# syma-wireless-charger.net
KiCad netlist of a schematic drawn in EAGLE
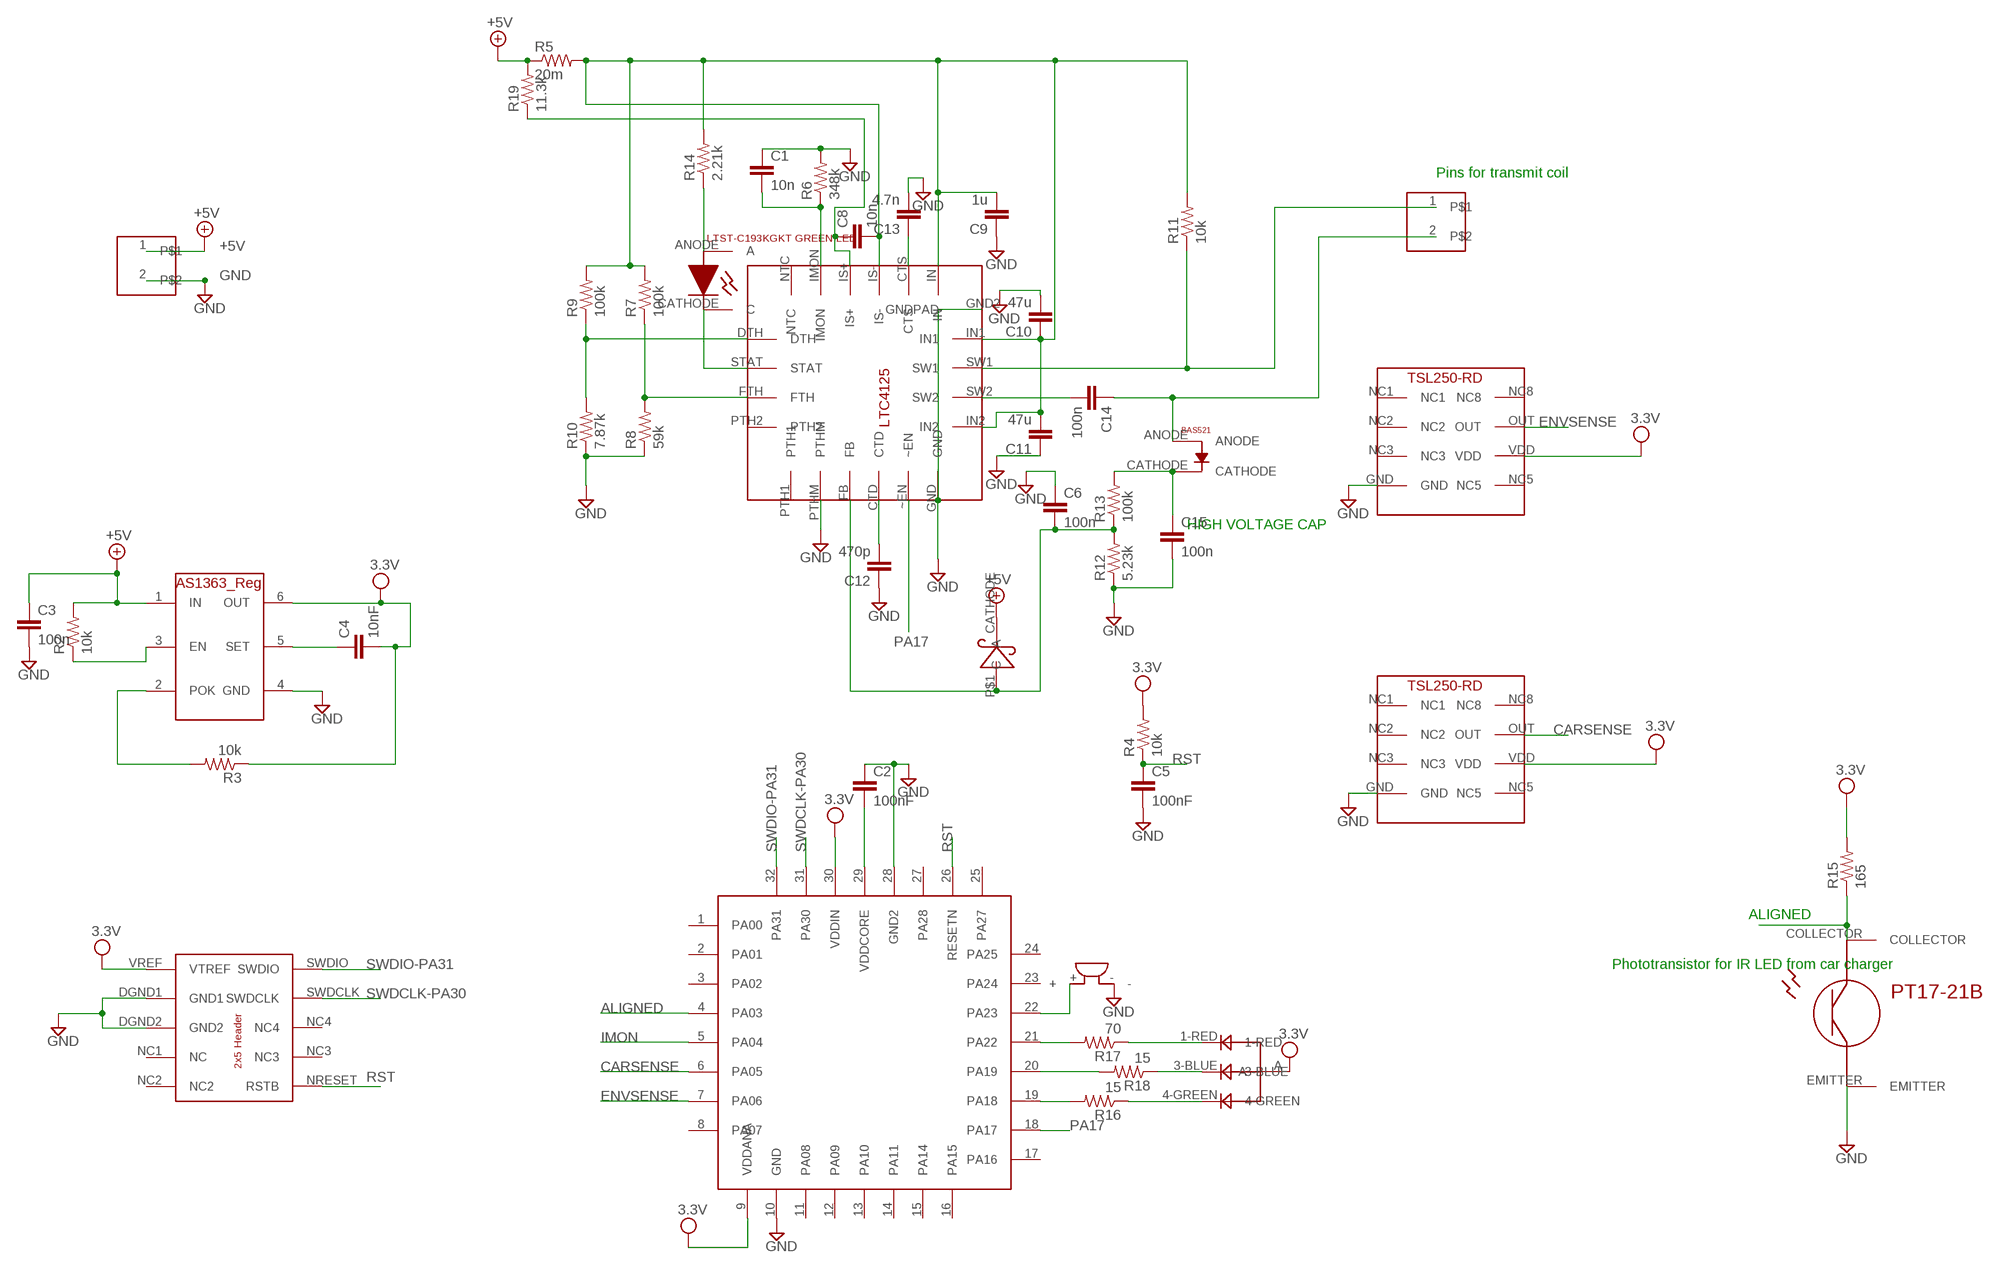
[diagram p0: schematic, sheet 1]

(export (version "E")
  (design (tool "Eeschema 10.0.6"))
  (components
    (comp (ref "C1")
      (value "10n")
      (footprint "eagle-import:C0805")
      (libsource (lib "eagle-import") (part "C-EUC0805"))
    )
    (comp (ref "C2")
      (value "100nF")
      (footprint "eagle-import:C0805K")
      (libsource (lib "eagle-import") (part "resistor_C-EUC0805K"))
    )
    (comp (ref "C3")
      (value "100n")
      (footprint "eagle-import:C0805K")
      (libsource (lib "eagle-import") (part "resistor_C-EUC0805K"))
    )
    (comp (ref "C4")
      (value "10nF")
      (footprint "eagle-import:C0805K")
      (libsource (lib "eagle-import") (part "resistor_C-EUC0805K"))
    )
    (comp (ref "C5")
      (value "100nF")
      (footprint "eagle-import:C0805K")
      (libsource (lib "eagle-import") (part "resistor_C-EUC0805K"))
    )
    (comp (ref "C6")
      (value "100n")
      (footprint "eagle-import:C0805")
      (libsource (lib "eagle-import") (part "C-EUC0805"))
    )
    (comp (ref "C8")
      (value "10n")
      (footprint "eagle-import:C0805")
      (libsource (lib "eagle-import") (part "C-EUC0805"))
    )
    (comp (ref "C9")
      (value "1u")
      (footprint "eagle-import:C0805")
      (libsource (lib "eagle-import") (part "C-EUC0805"))
    )
    (comp (ref "C10")
      (value "47u")
      (footprint "eagle-import:C0805")
      (libsource (lib "eagle-import") (part "C-EUC0805"))
    )
    (comp (ref "C11")
      (value "47u")
      (footprint "eagle-import:C0805")
      (libsource (lib "eagle-import") (part "C-EUC0805"))
    )
    (comp (ref "C12")
      (value "470p")
      (footprint "eagle-import:C0805")
      (libsource (lib "eagle-import") (part "C-EUC0805"))
    )
    (comp (ref "C13")
      (value "4.7n")
      (footprint "eagle-import:C0805")
      (libsource (lib "eagle-import") (part "C-EUC0805"))
    )
    (comp (ref "C14")
      (value "100n")
      (footprint "eagle-import:C1206")
      (libsource (lib "eagle-import") (part "C-EUC1206"))
    )
    (comp (ref "C15")
      (value "100n")
      (footprint "eagle-import:C0603")
      (libsource (lib "eagle-import") (part "resistor_C-EUC0603"))
    )
    (comp (ref "DBG1")
      (value "DEBUGHEAD")
      (footprint "eagle-import:DEBUGHEAD")
      (libsource (lib "eagle-import") (part "DEBUGHEAD"))
    )
    (comp (ref "R2")
      (value "10k")
      (footprint "eagle-import:R0805")
      (libsource (lib "eagle-import") (part "resistor_R-US_R0805"))
    )
    (comp (ref "R3")
      (value "10k")
      (footprint "eagle-import:R0805")
      (libsource (lib "eagle-import") (part "resistor_R-US_R0805"))
    )
    (comp (ref "R4")
      (value "10k")
      (footprint "eagle-import:R0805")
      (libsource (lib "eagle-import") (part "resistor_R-US_R0805"))
    )
    (comp (ref "R5")
      (value "20m")
      (footprint "eagle-import:R0805")
      (libsource (lib "eagle-import") (part "R-US_R0805"))
    )
    (comp (ref "R6")
      (value "348k")
      (footprint "eagle-import:R0805")
      (libsource (lib "eagle-import") (part "R-US_R0805"))
    )
    (comp (ref "R7")
      (value "100k")
      (footprint "eagle-import:R0805")
      (libsource (lib "eagle-import") (part "R-US_R0805"))
    )
    (comp (ref "R8")
      (value "59k")
      (footprint "eagle-import:R0805")
      (libsource (lib "eagle-import") (part "R-US_R0805"))
    )
    (comp (ref "R9")
      (value "100k")
      (footprint "eagle-import:R0805")
      (libsource (lib "eagle-import") (part "R-US_R0805"))
    )
    (comp (ref "R10")
      (value "7.87k")
      (footprint "eagle-import:R0805")
      (libsource (lib "eagle-import") (part "R-US_R0805"))
    )
    (comp (ref "R11")
      (value "10k")
      (footprint "eagle-import:R0805")
      (libsource (lib "eagle-import") (part "R-US_R0805"))
    )
    (comp (ref "R12")
      (value "5.23k")
      (footprint "eagle-import:R0805")
      (libsource (lib "eagle-import") (part "R-US_R0805"))
    )
    (comp (ref "R13")
      (value "100k")
      (footprint "eagle-import:R0805")
      (libsource (lib "eagle-import") (part "R-US_R0805"))
    )
    (comp (ref "R14")
      (value "2.21k")
      (footprint "eagle-import:R0805")
      (libsource (lib "eagle-import") (part "R-US_R0805"))
    )
    (comp (ref "R15")
      (value "165")
      (footprint "eagle-import:R0805")
      (libsource (lib "eagle-import") (part "resistor_R-US_R0805"))
    )
    (comp (ref "R16")
      (value "15")
      (footprint "eagle-import:R0805")
      (libsource (lib "eagle-import") (part "resistor_R-US_R0805"))
    )
    (comp (ref "R17")
      (value "70")
      (footprint "eagle-import:R0805")
      (libsource (lib "eagle-import") (part "resistor_R-US_R0805"))
    )
    (comp (ref "R18")
      (value "15")
      (footprint "eagle-import:R0805")
      (libsource (lib "eagle-import") (part "resistor_R-US_R0805"))
    )
    (comp (ref "R19")
      (value "11.3k")
      (footprint "eagle-import:R0805")
      (libsource (lib "eagle-import") (part "R-US_R0805"))
    )
    (comp (ref "U$1")
      (value "LTC4125")
      (footprint "eagle-import:LTC1945-QFN")
      (libsource (lib "eagle-import") (part "LTC4125"))
    )
    (comp (ref "U$2")
      (value "BAS521")
      (footprint "eagle-import:BAS521-V-DIODE")
      (libsource (lib "eagle-import") (part "BAS521"))
    )
    (comp (ref "U$3")
      (value "1X02")
      (footprint "eagle-import:1X02")
      (libsource (lib "eagle-import") (part "1X02"))
    )
    (comp (ref "U$4")
      (value "RGBLED")
      (footprint "eagle-import:RGBLED")
      (libsource (lib "eagle-import") (part "RGBLED"))
    )
    (comp (ref "U$5")
      (value "BUZZER")
      (footprint "eagle-import:BUZZER")
      (libsource (lib "eagle-import") (part "BUZZER"))
    )
    (comp (ref "U$6")
      (value "TSL250-RD")
      (footprint "eagle-import:TSL250-RD")
      (libsource (lib "eagle-import") (part "TSL250-RD"))
    )
    (comp (ref "U$7")
      (value "TSL250-RD")
      (footprint "eagle-import:TSL250-RD")
      (libsource (lib "eagle-import") (part "TSL250-RD"))
    )
    (comp (ref "U$8")
      (value "SCHTKYDIODE-523")
      (footprint "eagle-import:SOD-523")
      (libsource (lib "eagle-import") (part "SCHTKYDIODE-523"))
    )
    (comp (ref "U$9")
      (value "LTST-C193KGKT_GREEN-LED")
      (footprint "eagle-import:LTST-C193KGKT_GREEN-LED")
      (libsource (lib "eagle-import") (part "LTST-C193KGKT_GREEN-LED"))
    )
    (comp (ref "U$10")
      (value "PT17-21B_PHOTOTRANSISTOR")
      (footprint "eagle-import:PT17-21B_PHOTOTRANSISTOR")
      (libsource (lib "eagle-import") (part "PT17-21B_PHOTOTRANSISTOR"))
    )
    (comp (ref "U$11")
      (value "1X02")
      (footprint "eagle-import:1X02")
      (libsource (lib "eagle-import") (part "1X02"))
    )
    (comp (ref "U1")
      (value "SAMD21E")
      (footprint "eagle-import:TQFP32-08")
      (libsource (lib "eagle-import") (part "SAMD21E"))
    )
    (comp (ref "U2")
      (value "3.3V_AS1363")
      (footprint "eagle-import:SOT23-6")
      (libsource (lib "eagle-import") (part "3.3V_AS1363"))
    )
  )
  (nets
    (net (code "1") (name "+5V") (class "Default")
      (node (ref "C3") (pin "1") (pinfunction "1_1") (pintype "passive"))
      (node (ref "R19") (pin "2") (pinfunction "2_2") (pintype "passive"))
      (node (ref "R2") (pin "2") (pinfunction "2_2") (pintype "passive"))
      (node (ref "R5") (pin "1") (pinfunction "1_1") (pintype "passive"))
      (node (ref "U$3") (pin "1") (pinfunction "P$1_1") (pintype "bidirectional"))
      (node (ref "U$8") (pin "CATHODE") (pinfunction "C_CATHODE") (pintype "bidirectional"))
      (node (ref "U2") (pin "1") (pinfunction "IN_1") (pintype "bidirectional"))
    )
    (net (code "2") (name "/ALIGNED") (class "Default")
      (node (ref "R15") (pin "1") (pinfunction "1_1") (pintype "passive"))
      (node (ref "U$10") (pin "COLLECTOR") (pinfunction "COLLECTOR_COLLECTOR") (pintype "bidirectional"))
      (node (ref "U1") (pin "4") (pinfunction "PA03_4") (pintype "bidirectional"))
    )
    (net (code "3") (name "/CARSENSE") (class "Default")
      (node (ref "U$6") (pin "OUT") (pinfunction "OUT_OUT") (pintype "bidirectional"))
      (node (ref "U1") (pin "6") (pinfunction "PA05_6") (pintype "bidirectional"))
    )
    (net (code "4") (name "/ENVSENSE") (class "Default")
      (node (ref "U$7") (pin "OUT") (pinfunction "OUT_OUT") (pintype "bidirectional"))
      (node (ref "U1") (pin "7") (pinfunction "PA06_7") (pintype "bidirectional"))
    )
    (net (code "5") (name "/IMON") (class "Default")
      (node (ref "C1") (pin "2") (pinfunction "2_2") (pintype "passive"))
      (node (ref "R6") (pin "1") (pinfunction "1_1") (pintype "passive"))
      (node (ref "U$1") (pin "IMON") (pinfunction "IMON_IMON") (pintype "bidirectional"))
      (node (ref "U1") (pin "5") (pinfunction "PA04_5") (pintype "bidirectional"))
    )
    (net (code "6") (name "/PA17") (class "Default")
      (node (ref "U$1") (pin "~EN") (pinfunction "~{EN}_~EN") (pintype "bidirectional"))
      (node (ref "U1") (pin "18") (pinfunction "PA17_18") (pintype "bidirectional"))
    )
    (net (code "7") (name "/RST") (class "Default")
      (node (ref "C5") (pin "1") (pinfunction "1_1") (pintype "passive"))
      (node (ref "DBG1") (pin "NRESET") (pinfunction "RSTB_NRESET") (pintype "bidirectional"))
      (node (ref "R4") (pin "1") (pinfunction "1_1") (pintype "passive"))
      (node (ref "U1") (pin "26") (pinfunction "RESETN_26") (pintype "bidirectional"))
    )
    (net (code "8") (name "/SWDCLK-PA30") (class "Default")
      (node (ref "DBG1") (pin "SWDCLK") (pinfunction "SWDCLK_SWDCLK") (pintype "bidirectional"))
      (node (ref "U1") (pin "31") (pinfunction "PA30_31") (pintype "bidirectional"))
    )
    (net (code "9") (name "/SWDIO-PA31") (class "Default")
      (node (ref "DBG1") (pin "SWDIO") (pinfunction "SWDIO_SWDIO") (pintype "bidirectional"))
      (node (ref "U1") (pin "32") (pinfunction "PA31_32") (pintype "bidirectional"))
    )
    (net (code "10") (name "3.3V") (class "Default")
      (node (ref "C4") (pin "2") (pinfunction "2_2") (pintype "passive"))
      (node (ref "DBG1") (pin "VREF") (pinfunction "VTREF_VREF") (pintype "bidirectional"))
      (node (ref "R15") (pin "2") (pinfunction "2_2") (pintype "passive"))
      (node (ref "R3") (pin "1") (pinfunction "1_1") (pintype "passive"))
      (node (ref "R4") (pin "2") (pinfunction "2_2") (pintype "passive"))
      (node (ref "U$4") (pin "A") (pinfunction "A_A") (pintype "bidirectional"))
      (node (ref "U$6") (pin "VDD") (pinfunction "VDD_VDD") (pintype "bidirectional"))
      (node (ref "U$7") (pin "VDD") (pinfunction "VDD_VDD") (pintype "bidirectional"))
      (node (ref "U1") (pin "30") (pinfunction "VDDIN_30") (pintype "bidirectional"))
      (node (ref "U1") (pin "9") (pinfunction "VDDANA_9") (pintype "bidirectional"))
      (node (ref "U2") (pin "6") (pinfunction "OUT_6") (pintype "bidirectional"))
    )
    (net (code "11") (name "GND") (class "Default")
      (node (ref "C1") (pin "1") (pinfunction "1_1") (pintype "passive"))
      (node (ref "C10") (pin "2") (pinfunction "2_2") (pintype "passive"))
      (node (ref "C11") (pin "1") (pinfunction "1_1") (pintype "passive"))
      (node (ref "C12") (pin "1") (pinfunction "1_1") (pintype "passive"))
      (node (ref "C13") (pin "2") (pinfunction "2_2") (pintype "passive"))
      (node (ref "C15") (pin "2") (pinfunction "2_2") (pintype "passive"))
      (node (ref "C2") (pin "1") (pinfunction "1_1") (pintype "passive"))
      (node (ref "C3") (pin "2") (pinfunction "2_2") (pintype "passive"))
      (node (ref "C5") (pin "2") (pinfunction "2_2") (pintype "passive"))
      (node (ref "C6") (pin "1") (pinfunction "1_1") (pintype "passive"))
      (node (ref "C9") (pin "1") (pinfunction "1_1") (pintype "passive"))
      (node (ref "DBG1") (pin "DGND1") (pinfunction "GND1_DGND1") (pintype "bidirectional"))
      (node (ref "DBG1") (pin "DGND2") (pinfunction "GND2_DGND2") (pintype "bidirectional"))
      (node (ref "R10") (pin "1") (pinfunction "1_1") (pintype "passive"))
      (node (ref "R12") (pin "1") (pinfunction "1_1") (pintype "passive"))
      (node (ref "R6") (pin "2") (pinfunction "2_2") (pintype "passive"))
      (node (ref "R8") (pin "1") (pinfunction "1_1") (pintype "passive"))
      (node (ref "U$1") (pin "GND") (pinfunction "GND_GND") (pintype "bidirectional"))
      (node (ref "U$1") (pin "GND2") (pinfunction "GNDPAD_GND2") (pintype "bidirectional"))
      (node (ref "U$1") (pin "PTHM") (pinfunction "PTHM_PTHM") (pintype "bidirectional"))
      (node (ref "U$10") (pin "EMITTER") (pinfunction "EMITTER_EMITTER") (pintype "bidirectional"))
      (node (ref "U$3") (pin "2") (pinfunction "P$2_2") (pintype "bidirectional"))
      (node (ref "U$5") (pin "-") (pinfunction "-_-") (pintype "bidirectional"))
      (node (ref "U$6") (pin "GND") (pinfunction "GND_GND") (pintype "bidirectional"))
      (node (ref "U$7") (pin "GND") (pinfunction "GND_GND") (pintype "bidirectional"))
      (node (ref "U1") (pin "10") (pinfunction "GND_10") (pintype "bidirectional"))
      (node (ref "U1") (pin "28") (pinfunction "GND2_28") (pintype "bidirectional"))
      (node (ref "U2") (pin "4") (pinfunction "GND_4") (pintype "bidirectional"))
    )
    (net (code "12") (name "Net-(C8-Pad1)") (class "Default")
      (node (ref "C8") (pin "1") (pinfunction "1_1") (pintype "passive"))
      (node (ref "R19") (pin "1") (pinfunction "1_1") (pintype "passive"))
      (node (ref "U$1") (pin "IS+") (pinfunction "IS+_IS+") (pintype "bidirectional"))
    )
    (net (code "13") (name "Net-(C10-Pad1)") (class "Default")
      (node (ref "C10") (pin "1") (pinfunction "1_1") (pintype "passive"))
      (node (ref "C11") (pin "2") (pinfunction "2_2") (pintype "passive"))
      (node (ref "C8") (pin "2") (pinfunction "2_2") (pintype "passive"))
      (node (ref "C9") (pin "2") (pinfunction "2_2") (pintype "passive"))
      (node (ref "R11") (pin "2") (pinfunction "2_2") (pintype "passive"))
      (node (ref "R14") (pin "2") (pinfunction "2_2") (pintype "passive"))
      (node (ref "R5") (pin "2") (pinfunction "2_2") (pintype "passive"))
      (node (ref "R7") (pin "2") (pinfunction "2_2") (pintype "passive"))
      (node (ref "R9") (pin "2") (pinfunction "2_2") (pintype "passive"))
      (node (ref "U$1") (pin "IN") (pinfunction "IN_IN") (pintype "bidirectional"))
      (node (ref "U$1") (pin "IN1") (pinfunction "IN1_IN1") (pintype "bidirectional"))
      (node (ref "U$1") (pin "IN2") (pinfunction "IN2_IN2") (pintype "bidirectional"))
      (node (ref "U$1") (pin "IS-") (pinfunction "IS-_IS-") (pintype "bidirectional"))
    )
    (net (code "14") (name "Net-(C12-Pad2)") (class "Default")
      (node (ref "C12") (pin "2") (pinfunction "2_2") (pintype "passive"))
      (node (ref "U$1") (pin "CTD") (pinfunction "CTD_CTD") (pintype "bidirectional"))
    )
    (net (code "15") (name "Net-(C13-Pad1)") (class "Default")
      (node (ref "C13") (pin "1") (pinfunction "1_1") (pintype "passive"))
      (node (ref "U$1") (pin "CTS") (pinfunction "CTS_CTS") (pintype "bidirectional"))
    )
    (net (code "16") (name "Net-(C14-Pad2)") (class "Default")
      (node (ref "C14") (pin "2") (pinfunction "2_2") (pintype "passive"))
      (node (ref "U$1") (pin "SW2") (pinfunction "SW2_SW2") (pintype "bidirectional"))
    )
    (net (code "17") (name "Net-(C15-Pad1)") (class "Default")
      (node (ref "C15") (pin "1") (pinfunction "1_1") (pintype "passive"))
      (node (ref "R13") (pin "2") (pinfunction "2_2") (pintype "passive"))
      (node (ref "U$2") (pin "CATHODE") (pinfunction "CATHODE_CATHODE") (pintype "bidirectional"))
    )
    (net (code "18") (name "Net-(R7-Pad1)") (class "Default")
      (node (ref "R7") (pin "1") (pinfunction "1_1") (pintype "passive"))
      (node (ref "R8") (pin "2") (pinfunction "2_2") (pintype "passive"))
      (node (ref "U$1") (pin "FTH") (pinfunction "FTH_FTH") (pintype "bidirectional"))
    )
    (net (code "19") (name "Net-(R10-Pad2)") (class "Default")
      (node (ref "R10") (pin "2") (pinfunction "2_2") (pintype "passive"))
      (node (ref "R9") (pin "1") (pinfunction "1_1") (pintype "passive"))
      (node (ref "U$1") (pin "DTH") (pinfunction "DTH_DTH") (pintype "bidirectional"))
    )
    (net (code "20") (name "Net-(R16-Pad1)") (class "Default")
      (node (ref "R16") (pin "1") (pinfunction "1_1") (pintype "passive"))
      (node (ref "U$4") (pin "4-GREEN") (pinfunction "4-GREEN_4-GREEN") (pintype "bidirectional"))
    )
    (net (code "21") (name "Net-(R17-Pad1)") (class "Default")
      (node (ref "R17") (pin "1") (pinfunction "1_1") (pintype "passive"))
      (node (ref "U$4") (pin "1-RED") (pinfunction "1-RED_1-RED") (pintype "bidirectional"))
    )
    (net (code "22") (name "Net-(R18-Pad1)") (class "Default")
      (node (ref "R18") (pin "1") (pinfunction "1_1") (pintype "passive"))
      (node (ref "U$4") (pin "3-BLUE") (pinfunction "3-BLUE_3-BLUE") (pintype "bidirectional"))
    )
    (net (code "23") (name "Net-(U$8-A)") (class "Default")
      (node (ref "C6") (pin "2") (pinfunction "2_2") (pintype "passive"))
      (node (ref "R12") (pin "2") (pinfunction "2_2") (pintype "passive"))
      (node (ref "R13") (pin "1") (pinfunction "1_1") (pintype "passive"))
      (node (ref "U$1") (pin "FB") (pinfunction "FB_FB") (pintype "bidirectional"))
      (node (ref "U$8") (pin "P$1") (pinfunction "A_P$1") (pintype "bidirectional"))
    )
    (net (code "24") (name "Net-(U$9-A)") (class "Default")
      (node (ref "R14") (pin "1") (pinfunction "1_1") (pintype "passive"))
      (node (ref "U$9") (pin "ANODE") (pinfunction "A_ANODE") (pintype "bidirectional"))
    )
    (net (code "25") (name "Net-(U$9-C)") (class "Default")
      (node (ref "U$1") (pin "STAT") (pinfunction "STAT_STAT") (pintype "bidirectional"))
      (node (ref "U$9") (pin "CATHODE") (pinfunction "C_CATHODE") (pintype "bidirectional"))
    )
    (net (code "26") (name "Net-(U$11-P$1)") (class "Default")
      (node (ref "R11") (pin "1") (pinfunction "1_1") (pintype "passive"))
      (node (ref "U$1") (pin "SW1") (pinfunction "SW1_SW1") (pintype "bidirectional"))
      (node (ref "U$11") (pin "1") (pinfunction "P$1_1") (pintype "bidirectional"))
    )
    (net (code "27") (name "Net-(U$11-P$2)") (class "Default")
      (node (ref "C14") (pin "1") (pinfunction "1_1") (pintype "passive"))
      (node (ref "U$11") (pin "2") (pinfunction "P$2_2") (pintype "bidirectional"))
      (node (ref "U$2") (pin "ANODE") (pinfunction "ANODE_ANODE") (pintype "bidirectional"))
    )
    (net (code "28") (name "Net-(U1-PA18)") (class "Default")
      (node (ref "R16") (pin "2") (pinfunction "2_2") (pintype "passive"))
      (node (ref "U1") (pin "19") (pinfunction "PA18_19") (pintype "bidirectional"))
    )
    (net (code "29") (name "Net-(U1-PA19)") (class "Default")
      (node (ref "R18") (pin "2") (pinfunction "2_2") (pintype "passive"))
      (node (ref "U1") (pin "20") (pinfunction "PA19_20") (pintype "bidirectional"))
    )
    (net (code "30") (name "Net-(U1-PA22)") (class "Default")
      (node (ref "R17") (pin "2") (pinfunction "2_2") (pintype "passive"))
      (node (ref "U1") (pin "21") (pinfunction "PA22_21") (pintype "bidirectional"))
    )
    (net (code "31") (name "Net-(U1-PA23)") (class "Default")
      (node (ref "U$5") (pin "+") (pinfunction "+_+") (pintype "bidirectional"))
      (node (ref "U1") (pin "22") (pinfunction "PA23_22") (pintype "bidirectional"))
    )
    (net (code "32") (name "Net-(U1-VDDCORE)") (class "Default")
      (node (ref "C2") (pin "2") (pinfunction "2_2") (pintype "passive"))
      (node (ref "U1") (pin "29") (pinfunction "VDDCORE_29") (pintype "bidirectional"))
    )
    (net (code "33") (name "Net-(U2-EN)") (class "Default")
      (node (ref "R2") (pin "1") (pinfunction "1_1") (pintype "passive"))
      (node (ref "U2") (pin "3") (pinfunction "EN_3") (pintype "bidirectional"))
    )
    (net (code "34") (name "Net-(U2-POK)") (class "Default")
      (node (ref "R3") (pin "2") (pinfunction "2_2") (pintype "passive"))
      (node (ref "U2") (pin "2") (pinfunction "POK_2") (pintype "bidirectional"))
    )
    (net (code "35") (name "Net-(U2-SET)") (class "Default")
      (node (ref "C4") (pin "1") (pinfunction "1_1") (pintype "passive"))
      (node (ref "U2") (pin "5") (pinfunction "SET_5") (pintype "bidirectional"))
    )
    (net (code "36") (name "unconnected-(DBG1-NC-PadNC1)") (class "Default")
      (node (ref "DBG1") (pin "NC1") (pinfunction "NC_NC1") (pintype "bidirectional"))
    )
    (net (code "37") (name "unconnected-(DBG1-PadNC2)") (class "Default")
      (node (ref "DBG1") (pin "NC2") (pinfunction "NC2_NC2") (pintype "bidirectional"))
    )
    (net (code "38") (name "unconnected-(DBG1-PadNC3)") (class "Default")
      (node (ref "DBG1") (pin "NC3") (pinfunction "NC3_NC3") (pintype "bidirectional"))
    )
    (net (code "39") (name "unconnected-(DBG1-PadNC4)") (class "Default")
      (node (ref "DBG1") (pin "NC4") (pinfunction "NC4_NC4") (pintype "bidirectional"))
    )
    (net (code "40") (name "unconnected-(U$1-PadNTC)") (class "Default")
      (node (ref "U$1") (pin "NTC") (pinfunction "NTC_NTC") (pintype "bidirectional"))
    )
    (net (code "41") (name "unconnected-(U$1-PadPTH1)") (class "Default")
      (node (ref "U$1") (pin "PTH1") (pinfunction "PTH1_PTH1") (pintype "bidirectional"))
    )
    (net (code "42") (name "unconnected-(U$1-PadPTH2)") (class "Default")
      (node (ref "U$1") (pin "PTH2") (pinfunction "PTH2_PTH2") (pintype "bidirectional"))
    )
    (net (code "43") (name "unconnected-(U$6-PadNC1)") (class "Default")
      (node (ref "U$6") (pin "NC1") (pinfunction "NC1_NC1") (pintype "bidirectional"))
    )
    (net (code "44") (name "unconnected-(U$6-PadNC2)") (class "Default")
      (node (ref "U$6") (pin "NC2") (pinfunction "NC2_NC2") (pintype "bidirectional"))
    )
    (net (code "45") (name "unconnected-(U$6-PadNC3)") (class "Default")
      (node (ref "U$6") (pin "NC3") (pinfunction "NC3_NC3") (pintype "bidirectional"))
    )
    (net (code "46") (name "unconnected-(U$6-PadNC5)") (class "Default")
      (node (ref "U$6") (pin "NC5") (pinfunction "NC5_NC5") (pintype "bidirectional"))
    )
    (net (code "47") (name "unconnected-(U$6-PadNC8)") (class "Default")
      (node (ref "U$6") (pin "NC8") (pinfunction "NC8_NC8") (pintype "bidirectional"))
    )
    (net (code "48") (name "unconnected-(U$7-PadNC1)") (class "Default")
      (node (ref "U$7") (pin "NC1") (pinfunction "NC1_NC1") (pintype "bidirectional"))
    )
    (net (code "49") (name "unconnected-(U$7-PadNC2)") (class "Default")
      (node (ref "U$7") (pin "NC2") (pinfunction "NC2_NC2") (pintype "bidirectional"))
    )
    (net (code "50") (name "unconnected-(U$7-PadNC3)") (class "Default")
      (node (ref "U$7") (pin "NC3") (pinfunction "NC3_NC3") (pintype "bidirectional"))
    )
    (net (code "51") (name "unconnected-(U$7-PadNC5)") (class "Default")
      (node (ref "U$7") (pin "NC5") (pinfunction "NC5_NC5") (pintype "bidirectional"))
    )
    (net (code "52") (name "unconnected-(U$7-PadNC8)") (class "Default")
      (node (ref "U$7") (pin "NC8") (pinfunction "NC8_NC8") (pintype "bidirectional"))
    )
    (net (code "53") (name "unconnected-(U1-PA00-Pad1)") (class "Default")
      (node (ref "U1") (pin "1") (pinfunction "PA00_1") (pintype "bidirectional"))
    )
    (net (code "54") (name "unconnected-(U1-PA01-Pad2)") (class "Default")
      (node (ref "U1") (pin "2") (pinfunction "PA01_2") (pintype "bidirectional"))
    )
    (net (code "55") (name "unconnected-(U1-PA02-Pad3)") (class "Default")
      (node (ref "U1") (pin "3") (pinfunction "PA02_3") (pintype "bidirectional"))
    )
    (net (code "56") (name "unconnected-(U1-PA07-Pad8)") (class "Default")
      (node (ref "U1") (pin "8") (pinfunction "PA07_8") (pintype "bidirectional"))
    )
    (net (code "57") (name "unconnected-(U1-PA08-Pad11)") (class "Default")
      (node (ref "U1") (pin "11") (pinfunction "PA08_11") (pintype "bidirectional"))
    )
    (net (code "58") (name "unconnected-(U1-PA09-Pad12)") (class "Default")
      (node (ref "U1") (pin "12") (pinfunction "PA09_12") (pintype "bidirectional"))
    )
    (net (code "59") (name "unconnected-(U1-PA10-Pad13)") (class "Default")
      (node (ref "U1") (pin "13") (pinfunction "PA10_13") (pintype "bidirectional"))
    )
    (net (code "60") (name "unconnected-(U1-PA11-Pad14)") (class "Default")
      (node (ref "U1") (pin "14") (pinfunction "PA11_14") (pintype "bidirectional"))
    )
    (net (code "61") (name "unconnected-(U1-PA14-Pad15)") (class "Default")
      (node (ref "U1") (pin "15") (pinfunction "PA14_15") (pintype "bidirectional"))
    )
    (net (code "62") (name "unconnected-(U1-PA15-Pad16)") (class "Default")
      (node (ref "U1") (pin "16") (pinfunction "PA15_16") (pintype "bidirectional"))
    )
    (net (code "63") (name "unconnected-(U1-PA16-Pad17)") (class "Default")
      (node (ref "U1") (pin "17") (pinfunction "PA16_17") (pintype "bidirectional"))
    )
    (net (code "64") (name "unconnected-(U1-PA24-Pad23)") (class "Default")
      (node (ref "U1") (pin "23") (pinfunction "PA24_23") (pintype "bidirectional"))
    )
    (net (code "65") (name "unconnected-(U1-PA25-Pad24)") (class "Default")
      (node (ref "U1") (pin "24") (pinfunction "PA25_24") (pintype "bidirectional"))
    )
    (net (code "66") (name "unconnected-(U1-PA27-Pad25)") (class "Default")
      (node (ref "U1") (pin "25") (pinfunction "PA27_25") (pintype "bidirectional"))
    )
    (net (code "67") (name "unconnected-(U1-PA28-Pad27)") (class "Default")
      (node (ref "U1") (pin "27") (pinfunction "PA28_27") (pintype "bidirectional"))
    )
  )
)
